# Wise-1510-v1_0_0.net
KiCad netlist of a schematic drawn in EAGLE
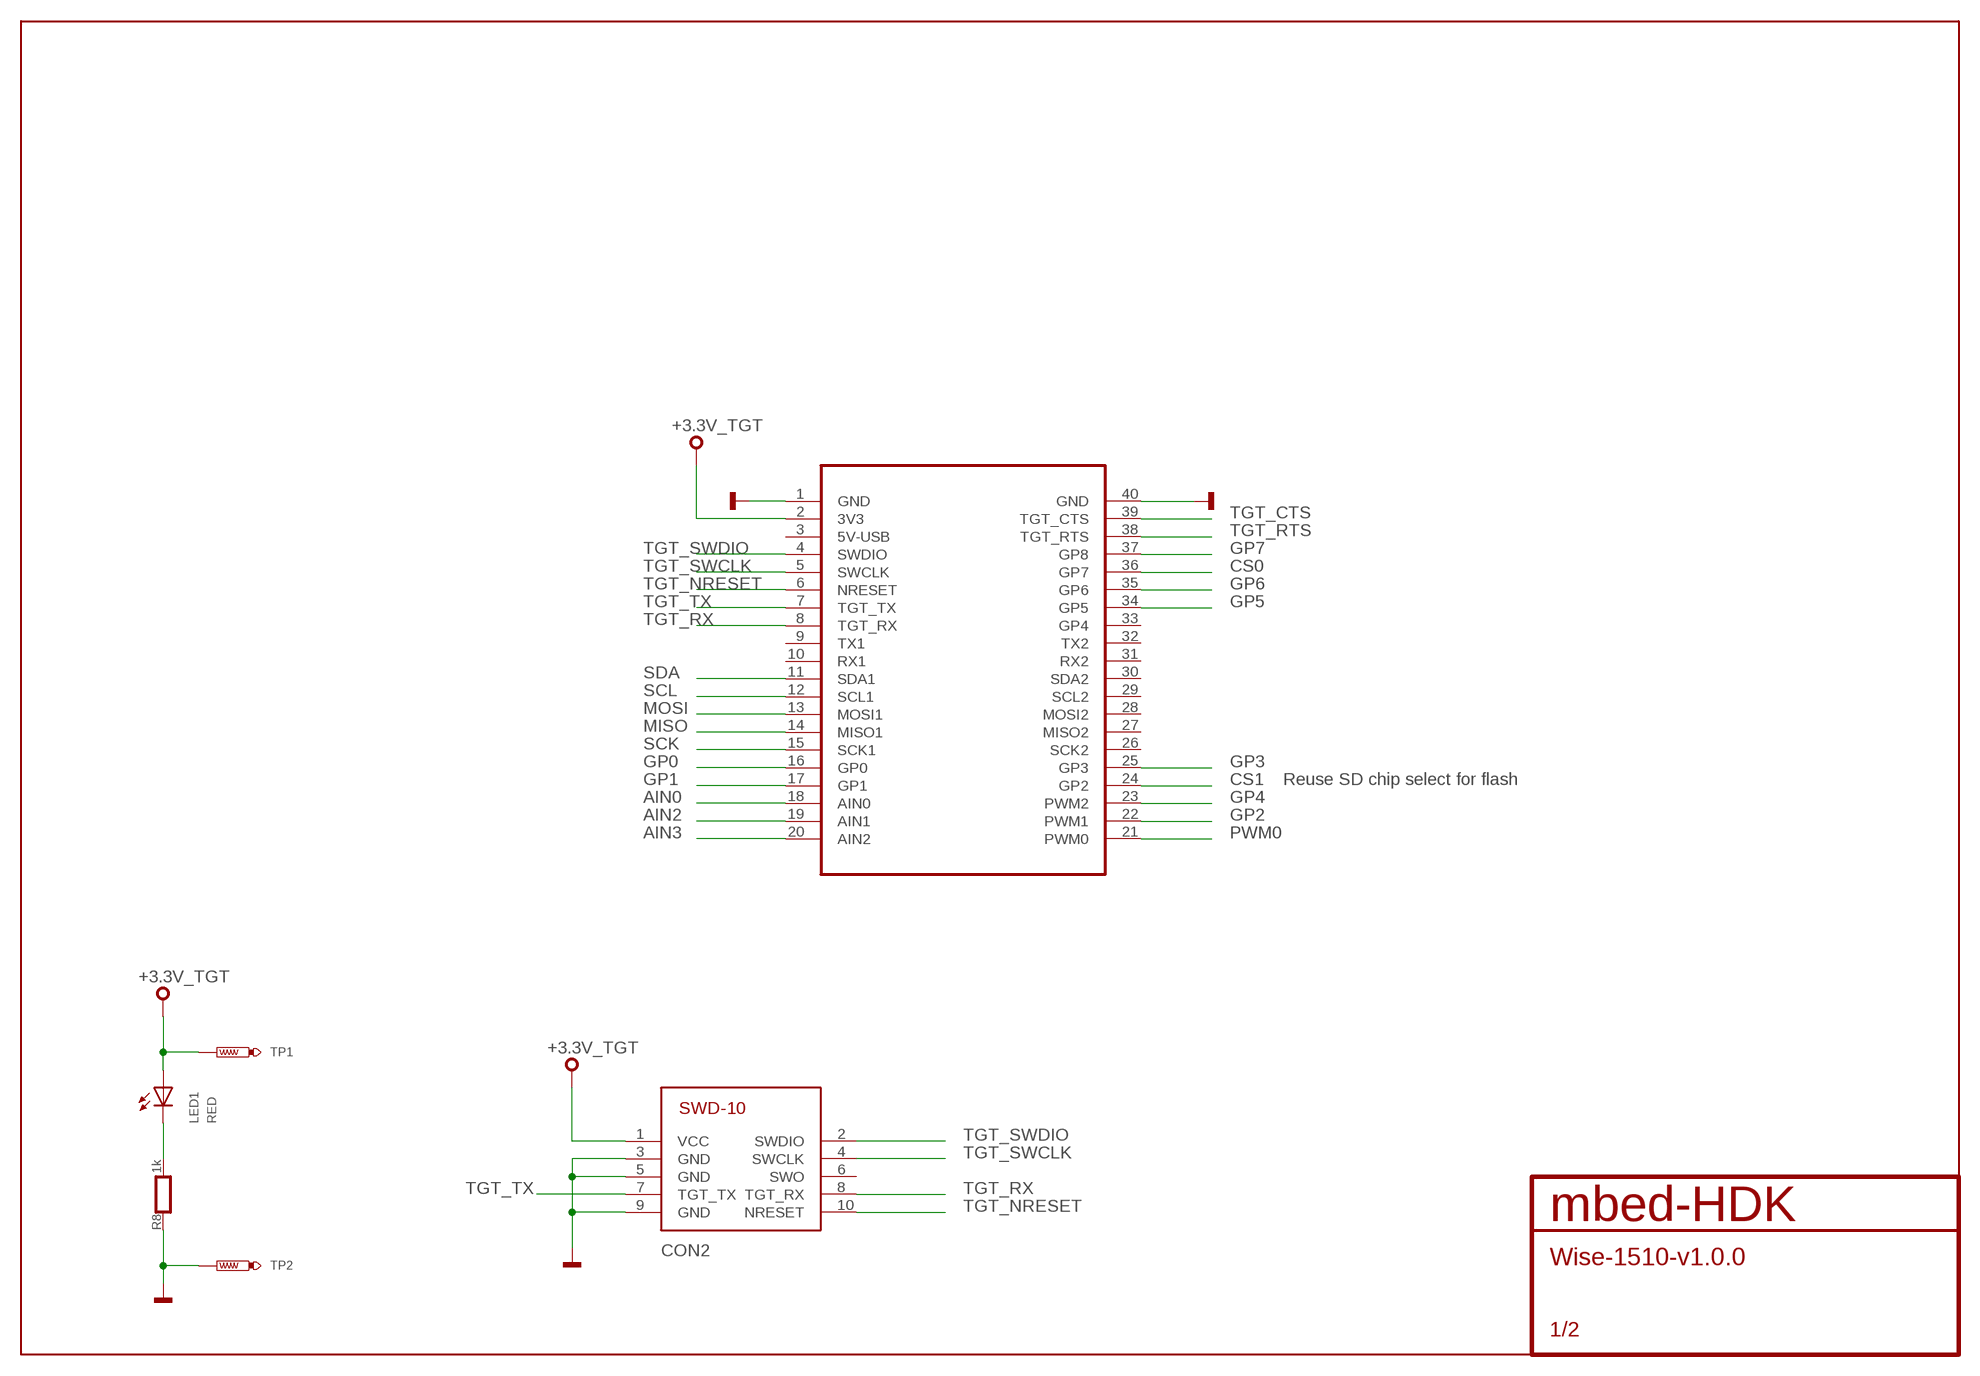
[diagram p0: schematic, sheet 1]
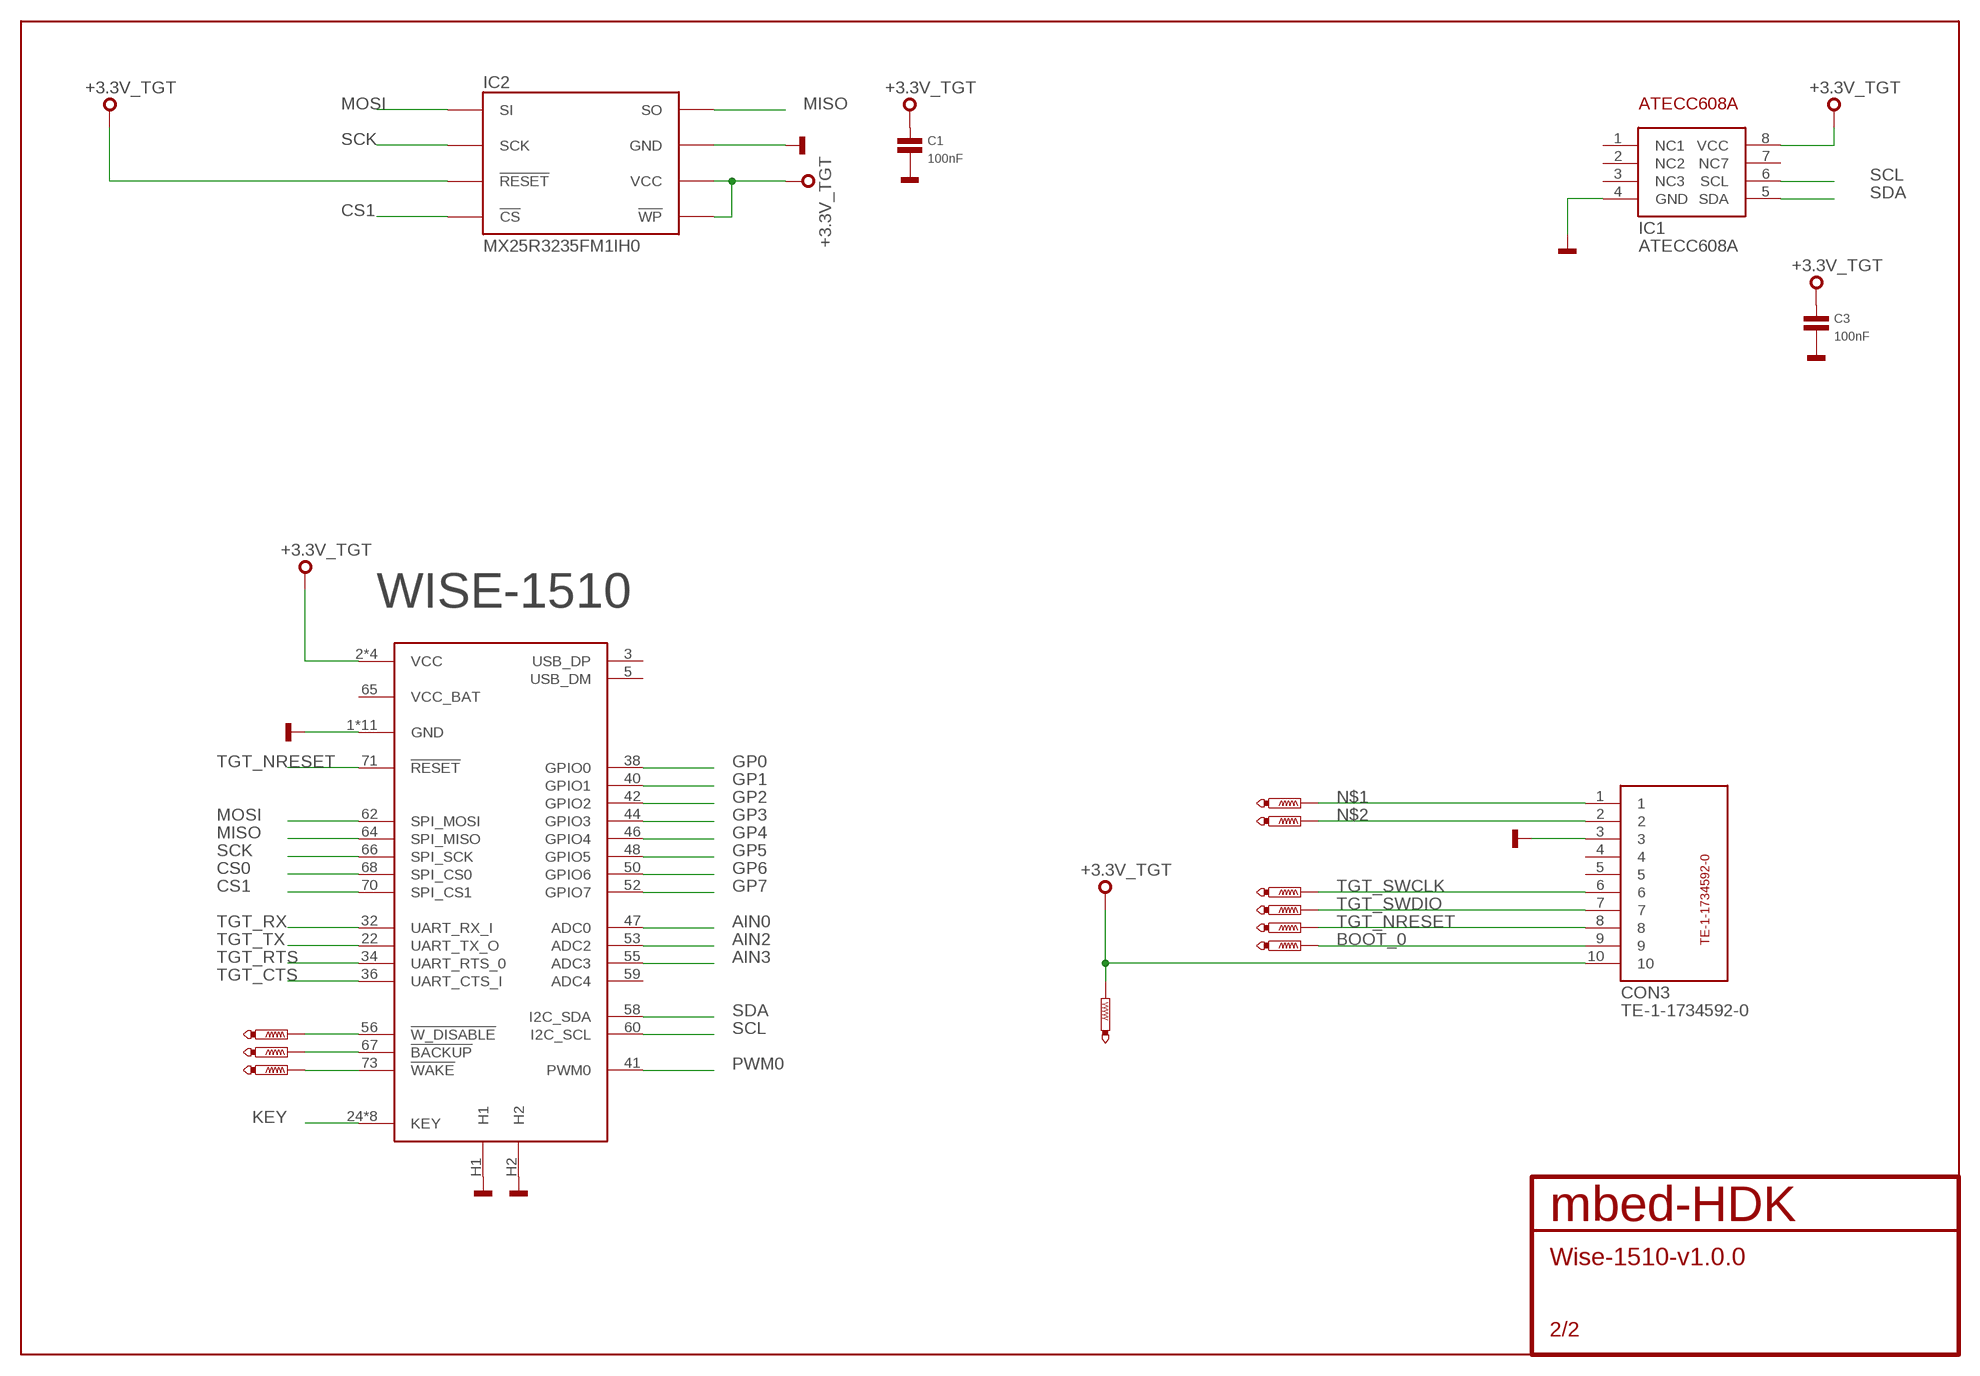
[diagram p1: schematic, sheet 2]

(export (version "E")
  (design (tool "Eeschema 10.0.6"))
  (components
    (comp (ref "CON2")
      (value "SWD-10/TC2050_SMD")
      (footprint "eagle-import:FTSH-105-02")
      (libsource (lib "eagle-import") (part "SWD-10/TC2050_SMD"))
    )
    (comp (ref "LED1")
      (value "RED")
      (footprint "eagle-import:CHIPLED_0603")
      (fields (field (name "MF") "Wurth Electronics Inc"))
      (libsource (lib "eagle-import") (part "SMD_LED0603"))
    )
    (comp (ref "R8")
      (value "1k")
      (footprint "eagle-import:0603")
      (libsource (lib "eagle-import") (part "RESISTOR0603"))
    )
    (comp (ref "TP1")
      (value "TEST-POINT-50R-PTH")
      (footprint "eagle-import:TP50-PTH")
      (libsource (lib "eagle-import") (part "TEST-POINT-50R-PTH"))
    )
    (comp (ref "TP2")
      (value "TEST-POINT-50R-PTH")
      (footprint "eagle-import:TP50-PTH")
      (libsource (lib "eagle-import") (part "TEST-POINT-50R-PTH"))
    )
    (comp (ref "U$1")
      (value "MODULE_DAUGHTER")
      (footprint "eagle-import:MODULE_DAUGHTER")
      (libsource (lib "eagle-import") (part "MODULE_DAUGHTER"))
    )
    (comp (ref "C1")
      (value "100nF")
      (footprint "eagle-import:0603")
      (libsource (lib "eagle-import") (part "CAPACITOR0603"))
    )
    (comp (ref "C3")
      (value "100nF")
      (footprint "eagle-import:0603")
      (libsource (lib "eagle-import") (part "CAPACITOR0603"))
    )
    (comp (ref "CON1")
      (value "WISE-1510_E")
      (footprint "eagle-import:MDT420E02001")
      (libsource (lib "eagle-import") (part "WISE-1510_E"))
    )
    (comp (ref "CON3")
      (value "TE-1-1734592-0")
      (footprint "eagle-import:TE-1-1734592-0")
      (libsource (lib "eagle-import") (part "TE-1-1734592-0"))
    )
    (comp (ref "IC1")
      (value "ATECC608A")
      (footprint "eagle-import:SO8")
      (libsource (lib "eagle-import") (part "ATECC608A"))
    )
    (comp (ref "IC2")
      (value "MX25R3235FM1IH0")
      (footprint "eagle-import:SO8")
      (fields (field (name "MF") "Macronix"))
      (libsource (lib "eagle-import") (part "MX25R3235FM1IH0"))
    )
    (comp (ref "TP3")
      (value "PTR1B1,27")
      (footprint "eagle-import:B1,27")
      (libsource (lib "eagle-import") (part "PTR1B1,27"))
    )
    (comp (ref "TP4")
      (value "PTR1B1,27")
      (footprint "eagle-import:B1,27")
      (libsource (lib "eagle-import") (part "PTR1B1,27"))
    )
    (comp (ref "TP5")
      (value "PTR1B1,27")
      (footprint "eagle-import:B1,27")
      (libsource (lib "eagle-import") (part "PTR1B1,27"))
    )
    (comp (ref "TP6")
      (value "PTR1B1,27")
      (footprint "eagle-import:B1,27")
      (libsource (lib "eagle-import") (part "PTR1B1,27"))
    )
    (comp (ref "TP7")
      (value "PTR1B1,27")
      (footprint "eagle-import:B1,27")
      (libsource (lib "eagle-import") (part "PTR1B1,27"))
    )
    (comp (ref "TP8")
      (value "PTR1B1,27")
      (footprint "eagle-import:B1,27")
      (libsource (lib "eagle-import") (part "PTR1B1,27"))
    )
    (comp (ref "TP9")
      (value "PTR1B1,27")
      (footprint "eagle-import:B1,27")
      (libsource (lib "eagle-import") (part "PTR1B1,27"))
    )
    (comp (ref "TP10")
      (value "PTR1B1,27")
      (footprint "eagle-import:B1,27")
      (libsource (lib "eagle-import") (part "PTR1B1,27"))
    )
    (comp (ref "TP11")
      (value "PTR1B1,27")
      (footprint "eagle-import:B1,27")
      (libsource (lib "eagle-import") (part "PTR1B1,27"))
    )
    (comp (ref "TP12")
      (value "PTR1B1,27")
      (footprint "eagle-import:B1,27")
      (libsource (lib "eagle-import") (part "PTR1B1,27"))
    )
  )
  (nets
    (net (code "1") (name "+3.3V_TGT") (class "Default")
      (node (ref "C1") (pin "1") (pinfunction "P$1_1") (pintype "passive"))
      (node (ref "C3") (pin "1") (pinfunction "P$1_1") (pintype "passive"))
      (node (ref "CON1") (pin "2") (pinfunction "VCC_2") (pintype "bidirectional"))
      (node (ref "CON1") (pin "4") (pinfunction "VCC_4") (pintype "bidirectional"))
      (node (ref "CON1") (pin "72") (pinfunction "VCC_72") (pintype "bidirectional"))
      (node (ref "CON1") (pin "74") (pinfunction "VCC_74") (pintype "bidirectional"))
      (node (ref "CON2") (pin "1") (pinfunction "VCC_1") (pintype "bidirectional"))
      (node (ref "CON3") (pin "10") (pinfunction "10_10") (pintype "bidirectional"))
      (node (ref "IC1") (pin "8") (pinfunction "VCC_8") (pintype "bidirectional"))
      (node (ref "IC2") (pin "3") (pinfunction "~{WP}_3") (pintype "bidirectional"))
      (node (ref "IC2") (pin "7") (pinfunction "~{RESET}_7") (pintype "bidirectional"))
      (node (ref "IC2") (pin "8") (pinfunction "VCC_8") (pintype "bidirectional"))
      (node (ref "LED1") (pin "A") (pinfunction "A_A") (pintype "passive"))
      (node (ref "TP1") (pin "TP") (pinfunction "TP_TP") (pintype "input"))
      (node (ref "TP12") (pin "TP") (pinfunction "TP_TP") (pintype "input"))
      (node (ref "U$1") (pin "2") (pinfunction "3V3_2") (pintype "bidirectional"))
    )
    (net (code "2") (name "AIN0") (class "Default")
      (node (ref "CON1") (pin "47") (pinfunction "ADC0_47") (pintype "bidirectional"))
      (node (ref "U$1") (pin "18") (pinfunction "AIN0_18") (pintype "bidirectional"))
    )
    (net (code "3") (name "AIN2") (class "Default")
      (node (ref "CON1") (pin "53") (pinfunction "ADC2_53") (pintype "bidirectional"))
      (node (ref "U$1") (pin "19") (pinfunction "AIN1_19") (pintype "bidirectional"))
    )
    (net (code "4") (name "AIN3") (class "Default")
      (node (ref "CON1") (pin "55") (pinfunction "ADC3_55") (pintype "bidirectional"))
      (node (ref "U$1") (pin "20") (pinfunction "AIN2_20") (pintype "bidirectional"))
    )
    (net (code "5") (name "BOOT_0") (class "Default")
      (node (ref "CON3") (pin "9") (pinfunction "9_9") (pintype "bidirectional"))
      (node (ref "TP8") (pin "TP") (pinfunction "TP_TP") (pintype "input"))
    )
    (net (code "6") (name "CS0") (class "Default")
      (node (ref "CON1") (pin "68") (pinfunction "SPI_CS0_68") (pintype "bidirectional"))
      (node (ref "U$1") (pin "36") (pinfunction "GP7_36") (pintype "bidirectional"))
    )
    (net (code "7") (name "CS1") (class "Default")
      (node (ref "CON1") (pin "70") (pinfunction "SPI_CS1_70") (pintype "bidirectional"))
      (node (ref "IC2") (pin "1") (pinfunction "~{CS}_1") (pintype "bidirectional"))
      (node (ref "U$1") (pin "24") (pinfunction "GP2_24") (pintype "bidirectional"))
    )
    (net (code "8") (name "GND") (class "Default")
      (node (ref "C1") (pin "2") (pinfunction "P$2_2") (pintype "passive"))
      (node (ref "C3") (pin "2") (pinfunction "P$2_2") (pintype "passive"))
      (node (ref "CON1") (pin "1") (pinfunction "GND_1") (pintype "bidirectional"))
      (node (ref "CON1") (pin "18") (pinfunction "GND_18") (pintype "bidirectional"))
      (node (ref "CON1") (pin "33") (pinfunction "GND_33") (pintype "bidirectional"))
      (node (ref "CON1") (pin "39") (pinfunction "GND_39") (pintype "bidirectional"))
      (node (ref "CON1") (pin "45") (pinfunction "GND_45") (pintype "bidirectional"))
      (node (ref "CON1") (pin "51") (pinfunction "GND_51") (pintype "bidirectional"))
      (node (ref "CON1") (pin "57") (pinfunction "GND_57") (pintype "bidirectional"))
      (node (ref "CON1") (pin "63") (pinfunction "GND_63") (pintype "bidirectional"))
      (node (ref "CON1") (pin "69") (pinfunction "GND_69") (pintype "bidirectional"))
      (node (ref "CON1") (pin "7") (pinfunction "GND_7") (pintype "bidirectional"))
      (node (ref "CON1") (pin "75") (pinfunction "GND_75") (pintype "bidirectional"))
      (node (ref "CON1") (pin "H1") (pinfunction "H1_H1") (pintype "bidirectional"))
      (node (ref "CON1") (pin "H2") (pinfunction "H2_H2") (pintype "bidirectional"))
      (node (ref "CON2") (pin "3") (pinfunction "GND_3") (pintype "bidirectional"))
      (node (ref "CON2") (pin "5") (pinfunction "GND_5") (pintype "bidirectional"))
      (node (ref "CON2") (pin "9") (pinfunction "GND_9") (pintype "bidirectional"))
      (node (ref "CON3") (pin "3") (pinfunction "3_3") (pintype "bidirectional"))
      (node (ref "IC1") (pin "4") (pinfunction "GND_4") (pintype "bidirectional"))
      (node (ref "IC2") (pin "4") (pinfunction "GND_4") (pintype "bidirectional"))
      (node (ref "R8") (pin "1") (pinfunction "P$1_1") (pintype "passive"))
      (node (ref "TP2") (pin "TP") (pinfunction "TP_TP") (pintype "input"))
      (node (ref "U$1") (pin "1") (pinfunction "GND_1") (pintype "bidirectional"))
      (node (ref "U$1") (pin "40") (pinfunction "GND_40") (pintype "bidirectional"))
    )
    (net (code "9") (name "GP0") (class "Default")
      (node (ref "CON1") (pin "38") (pinfunction "GPIO0_38") (pintype "bidirectional"))
      (node (ref "U$1") (pin "16") (pinfunction "GP0_16") (pintype "bidirectional"))
    )
    (net (code "10") (name "GP1") (class "Default")
      (node (ref "CON1") (pin "40") (pinfunction "GPIO1_40") (pintype "bidirectional"))
      (node (ref "U$1") (pin "17") (pinfunction "GP1_17") (pintype "bidirectional"))
    )
    (net (code "11") (name "GP2") (class "Default")
      (node (ref "CON1") (pin "42") (pinfunction "GPIO2_42") (pintype "bidirectional"))
      (node (ref "U$1") (pin "22") (pinfunction "PWM1_22") (pintype "bidirectional"))
    )
    (net (code "12") (name "GP3") (class "Default")
      (node (ref "CON1") (pin "44") (pinfunction "GPIO3_44") (pintype "bidirectional"))
      (node (ref "U$1") (pin "25") (pinfunction "GP3_25") (pintype "bidirectional"))
    )
    (net (code "13") (name "GP4") (class "Default")
      (node (ref "CON1") (pin "46") (pinfunction "GPIO4_46") (pintype "bidirectional"))
      (node (ref "U$1") (pin "23") (pinfunction "PWM2_23") (pintype "bidirectional"))
    )
    (net (code "14") (name "GP5") (class "Default")
      (node (ref "CON1") (pin "48") (pinfunction "GPIO5_48") (pintype "bidirectional"))
      (node (ref "U$1") (pin "34") (pinfunction "GP5_34") (pintype "bidirectional"))
    )
    (net (code "15") (name "GP6") (class "Default")
      (node (ref "CON1") (pin "50") (pinfunction "GPIO6_50") (pintype "bidirectional"))
      (node (ref "U$1") (pin "35") (pinfunction "GP6_35") (pintype "bidirectional"))
    )
    (net (code "16") (name "GP7") (class "Default")
      (node (ref "CON1") (pin "52") (pinfunction "GPIO7_52") (pintype "bidirectional"))
      (node (ref "U$1") (pin "37") (pinfunction "GP8_37") (pintype "bidirectional"))
    )
    (net (code "17") (name "KEY") (class "Default")
      (node (ref "CON1") (pin "24") (pinfunction "KEY_24") (pintype "bidirectional"))
      (node (ref "CON1") (pin "25") (pinfunction "KEY_25") (pintype "bidirectional"))
      (node (ref "CON1") (pin "26") (pinfunction "KEY_26") (pintype "bidirectional"))
      (node (ref "CON1") (pin "27") (pinfunction "KEY_27") (pintype "bidirectional"))
      (node (ref "CON1") (pin "28") (pinfunction "KEY_28") (pintype "bidirectional"))
      (node (ref "CON1") (pin "29") (pinfunction "KEY_29") (pintype "bidirectional"))
      (node (ref "CON1") (pin "30") (pinfunction "KEY_30") (pintype "bidirectional"))
      (node (ref "CON1") (pin "31") (pinfunction "KEY_31") (pintype "bidirectional"))
    )
    (net (code "18") (name "MISO") (class "Default")
      (node (ref "CON1") (pin "64") (pinfunction "SPI_MISO_64") (pintype "bidirectional"))
      (node (ref "IC2") (pin "2") (pinfunction "SO_2") (pintype "bidirectional"))
      (node (ref "U$1") (pin "14") (pinfunction "MISO1_14") (pintype "bidirectional"))
    )
    (net (code "19") (name "MOSI") (class "Default")
      (node (ref "CON1") (pin "62") (pinfunction "SPI_MOSI_62") (pintype "bidirectional"))
      (node (ref "IC2") (pin "5") (pinfunction "SI_5") (pintype "bidirectional"))
      (node (ref "U$1") (pin "13") (pinfunction "MOSI1_13") (pintype "bidirectional"))
    )
    (net (code "20") (name "N$1") (class "Default")
      (node (ref "CON3") (pin "1") (pinfunction "1_1") (pintype "bidirectional"))
      (node (ref "TP7") (pin "TP") (pinfunction "TP_TP") (pintype "input"))
    )
    (net (code "21") (name "N$2") (class "Default")
      (node (ref "CON3") (pin "2") (pinfunction "2_2") (pintype "bidirectional"))
      (node (ref "TP6") (pin "TP") (pinfunction "TP_TP") (pintype "input"))
    )
    (net (code "22") (name "Net-(CON1-~{BACKUP})") (class "Default")
      (node (ref "CON1") (pin "67") (pinfunction "~{BACKUP}_67") (pintype "bidirectional"))
      (node (ref "TP10") (pin "TP") (pinfunction "TP_TP") (pintype "input"))
    )
    (net (code "23") (name "Net-(CON1-~{WAKE})") (class "Default")
      (node (ref "CON1") (pin "73") (pinfunction "~{WAKE}_73") (pintype "bidirectional"))
      (node (ref "TP11") (pin "TP") (pinfunction "TP_TP") (pintype "input"))
    )
    (net (code "24") (name "Net-(CON1-~{W_DISABLE})") (class "Default")
      (node (ref "CON1") (pin "56") (pinfunction "~{W_DISABLE}_56") (pintype "bidirectional"))
      (node (ref "TP9") (pin "TP") (pinfunction "TP_TP") (pintype "input"))
    )
    (net (code "25") (name "Net-(R8-P$2)") (class "Default")
      (node (ref "LED1") (pin "C") (pinfunction "C_C") (pintype "passive"))
      (node (ref "R8") (pin "2") (pinfunction "P$2_2") (pintype "passive"))
    )
    (net (code "26") (name "PWM0") (class "Default")
      (node (ref "CON1") (pin "41") (pinfunction "PWM0_41") (pintype "bidirectional"))
      (node (ref "U$1") (pin "21") (pinfunction "PWM0_21") (pintype "bidirectional"))
    )
    (net (code "27") (name "SCK") (class "Default")
      (node (ref "CON1") (pin "66") (pinfunction "SPI_SCK_66") (pintype "bidirectional"))
      (node (ref "IC2") (pin "6") (pinfunction "SCK_6") (pintype "bidirectional"))
      (node (ref "U$1") (pin "15") (pinfunction "SCK1_15") (pintype "bidirectional"))
    )
    (net (code "28") (name "SCL") (class "Default")
      (node (ref "CON1") (pin "60") (pinfunction "I2C_SCL_60") (pintype "bidirectional"))
      (node (ref "IC1") (pin "6") (pinfunction "SCL_6") (pintype "bidirectional"))
      (node (ref "U$1") (pin "12") (pinfunction "SCL1_12") (pintype "bidirectional"))
    )
    (net (code "29") (name "SDA") (class "Default")
      (node (ref "CON1") (pin "58") (pinfunction "I2C_SDA_58") (pintype "bidirectional"))
      (node (ref "IC1") (pin "5") (pinfunction "SDA_5") (pintype "bidirectional"))
      (node (ref "U$1") (pin "11") (pinfunction "SDA1_11") (pintype "bidirectional"))
    )
    (net (code "30") (name "TGT_CTS") (class "Default")
      (node (ref "CON1") (pin "36") (pinfunction "UART_CTS_I_36") (pintype "bidirectional"))
      (node (ref "U$1") (pin "39") (pinfunction "TGT_CTS_39") (pintype "bidirectional"))
    )
    (net (code "31") (name "TGT_NRESET") (class "Default")
      (node (ref "CON1") (pin "71") (pinfunction "~{RESET}_71") (pintype "bidirectional"))
      (node (ref "CON2") (pin "10") (pinfunction "NRESET_10") (pintype "bidirectional"))
      (node (ref "CON3") (pin "8") (pinfunction "8_8") (pintype "bidirectional"))
      (node (ref "TP5") (pin "TP") (pinfunction "TP_TP") (pintype "input"))
      (node (ref "U$1") (pin "6") (pinfunction "NRESET_6") (pintype "bidirectional"))
    )
    (net (code "32") (name "TGT_RTS") (class "Default")
      (node (ref "CON1") (pin "34") (pinfunction "UART_RTS_0_34") (pintype "bidirectional"))
      (node (ref "U$1") (pin "38") (pinfunction "TGT_RTS_38") (pintype "bidirectional"))
    )
    (net (code "33") (name "TGT_RX") (class "Default")
      (node (ref "CON1") (pin "32") (pinfunction "UART_RX_I_32") (pintype "bidirectional"))
      (node (ref "CON2") (pin "8") (pinfunction "TGT_RX_8") (pintype "bidirectional"))
      (node (ref "U$1") (pin "8") (pinfunction "TGT_RX_8") (pintype "bidirectional"))
    )
    (net (code "34") (name "TGT_SWCLK") (class "Default")
      (node (ref "CON2") (pin "4") (pinfunction "SWCLK_4") (pintype "bidirectional"))
      (node (ref "CON3") (pin "6") (pinfunction "6_6") (pintype "bidirectional"))
      (node (ref "TP3") (pin "TP") (pinfunction "TP_TP") (pintype "input"))
      (node (ref "U$1") (pin "5") (pinfunction "SWCLK_5") (pintype "bidirectional"))
    )
    (net (code "35") (name "TGT_SWDIO") (class "Default")
      (node (ref "CON2") (pin "2") (pinfunction "SWDIO_2") (pintype "bidirectional"))
      (node (ref "CON3") (pin "7") (pinfunction "7_7") (pintype "bidirectional"))
      (node (ref "TP4") (pin "TP") (pinfunction "TP_TP") (pintype "input"))
      (node (ref "U$1") (pin "4") (pinfunction "SWDIO_4") (pintype "bidirectional"))
    )
    (net (code "36") (name "TGT_TX") (class "Default")
      (node (ref "CON1") (pin "22") (pinfunction "UART_TX_O_22") (pintype "bidirectional"))
      (node (ref "CON2") (pin "7") (pinfunction "TGT_TX_7") (pintype "bidirectional"))
      (node (ref "U$1") (pin "7") (pinfunction "TGT_TX_7") (pintype "bidirectional"))
    )
    (net (code "37") (name "unconnected-(CON1-ADC4-Pad59)") (class "Default")
      (node (ref "CON1") (pin "59") (pinfunction "ADC4_59") (pintype "bidirectional"))
    )
    (net (code "38") (name "unconnected-(CON1-USB_DM-Pad5)") (class "Default")
      (node (ref "CON1") (pin "5") (pinfunction "USB_DM_5") (pintype "bidirectional"))
    )
    (net (code "39") (name "unconnected-(CON1-USB_DP-Pad3)") (class "Default")
      (node (ref "CON1") (pin "3") (pinfunction "USB_DP_3") (pintype "bidirectional"))
    )
    (net (code "40") (name "unconnected-(CON1-VCC_BAT-Pad65)") (class "Default")
      (node (ref "CON1") (pin "65") (pinfunction "VCC_BAT_65") (pintype "bidirectional"))
    )
    (net (code "41") (name "unconnected-(CON2-SWO-Pad6)") (class "Default")
      (node (ref "CON2") (pin "6") (pinfunction "SWO_6") (pintype "bidirectional"))
    )
    (net (code "42") (name "unconnected-(CON3-Pad4)") (class "Default")
      (node (ref "CON3") (pin "4") (pinfunction "4_4") (pintype "bidirectional"))
    )
    (net (code "43") (name "unconnected-(CON3-Pad5)") (class "Default")
      (node (ref "CON3") (pin "5") (pinfunction "5_5") (pintype "bidirectional"))
    )
    (net (code "44") (name "unconnected-(IC1-NC1-Pad1)") (class "Default")
      (node (ref "IC1") (pin "1") (pinfunction "NC1_1") (pintype "bidirectional"))
    )
    (net (code "45") (name "unconnected-(IC1-NC2-Pad2)") (class "Default")
      (node (ref "IC1") (pin "2") (pinfunction "NC2_2") (pintype "bidirectional"))
    )
    (net (code "46") (name "unconnected-(IC1-NC3-Pad3)") (class "Default")
      (node (ref "IC1") (pin "3") (pinfunction "NC3_3") (pintype "bidirectional"))
    )
    (net (code "47") (name "unconnected-(IC1-NC7-Pad7)") (class "Default")
      (node (ref "IC1") (pin "7") (pinfunction "NC7_7") (pintype "bidirectional"))
    )
    (net (code "48") (name "unconnected-(U$1-5V-USB-Pad3)") (class "Default")
      (node (ref "U$1") (pin "3") (pinfunction "5V-USB_3") (pintype "bidirectional"))
    )
    (net (code "49") (name "unconnected-(U$1-GP4-Pad33)") (class "Default")
      (node (ref "U$1") (pin "33") (pinfunction "GP4_33") (pintype "bidirectional"))
    )
    (net (code "50") (name "unconnected-(U$1-MISO2-Pad27)") (class "Default")
      (node (ref "U$1") (pin "27") (pinfunction "MISO2_27") (pintype "bidirectional"))
    )
    (net (code "51") (name "unconnected-(U$1-MOSI2-Pad28)") (class "Default")
      (node (ref "U$1") (pin "28") (pinfunction "MOSI2_28") (pintype "bidirectional"))
    )
    (net (code "52") (name "unconnected-(U$1-RX1-Pad10)") (class "Default")
      (node (ref "U$1") (pin "10") (pinfunction "RX1_10") (pintype "bidirectional"))
    )
    (net (code "53") (name "unconnected-(U$1-RX2-Pad31)") (class "Default")
      (node (ref "U$1") (pin "31") (pinfunction "RX2_31") (pintype "bidirectional"))
    )
    (net (code "54") (name "unconnected-(U$1-SCK2-Pad26)") (class "Default")
      (node (ref "U$1") (pin "26") (pinfunction "SCK2_26") (pintype "bidirectional"))
    )
    (net (code "55") (name "unconnected-(U$1-SCL2-Pad29)") (class "Default")
      (node (ref "U$1") (pin "29") (pinfunction "SCL2_29") (pintype "bidirectional"))
    )
    (net (code "56") (name "unconnected-(U$1-SDA2-Pad30)") (class "Default")
      (node (ref "U$1") (pin "30") (pinfunction "SDA2_30") (pintype "bidirectional"))
    )
    (net (code "57") (name "unconnected-(U$1-TX1-Pad9)") (class "Default")
      (node (ref "U$1") (pin "9") (pinfunction "TX1_9") (pintype "bidirectional"))
    )
    (net (code "58") (name "unconnected-(U$1-TX2-Pad32)") (class "Default")
      (node (ref "U$1") (pin "32") (pinfunction "TX2_32") (pintype "bidirectional"))
    )
  )
)
